# ttl.net
KiCad netlist of a schematic drawn in EAGLE
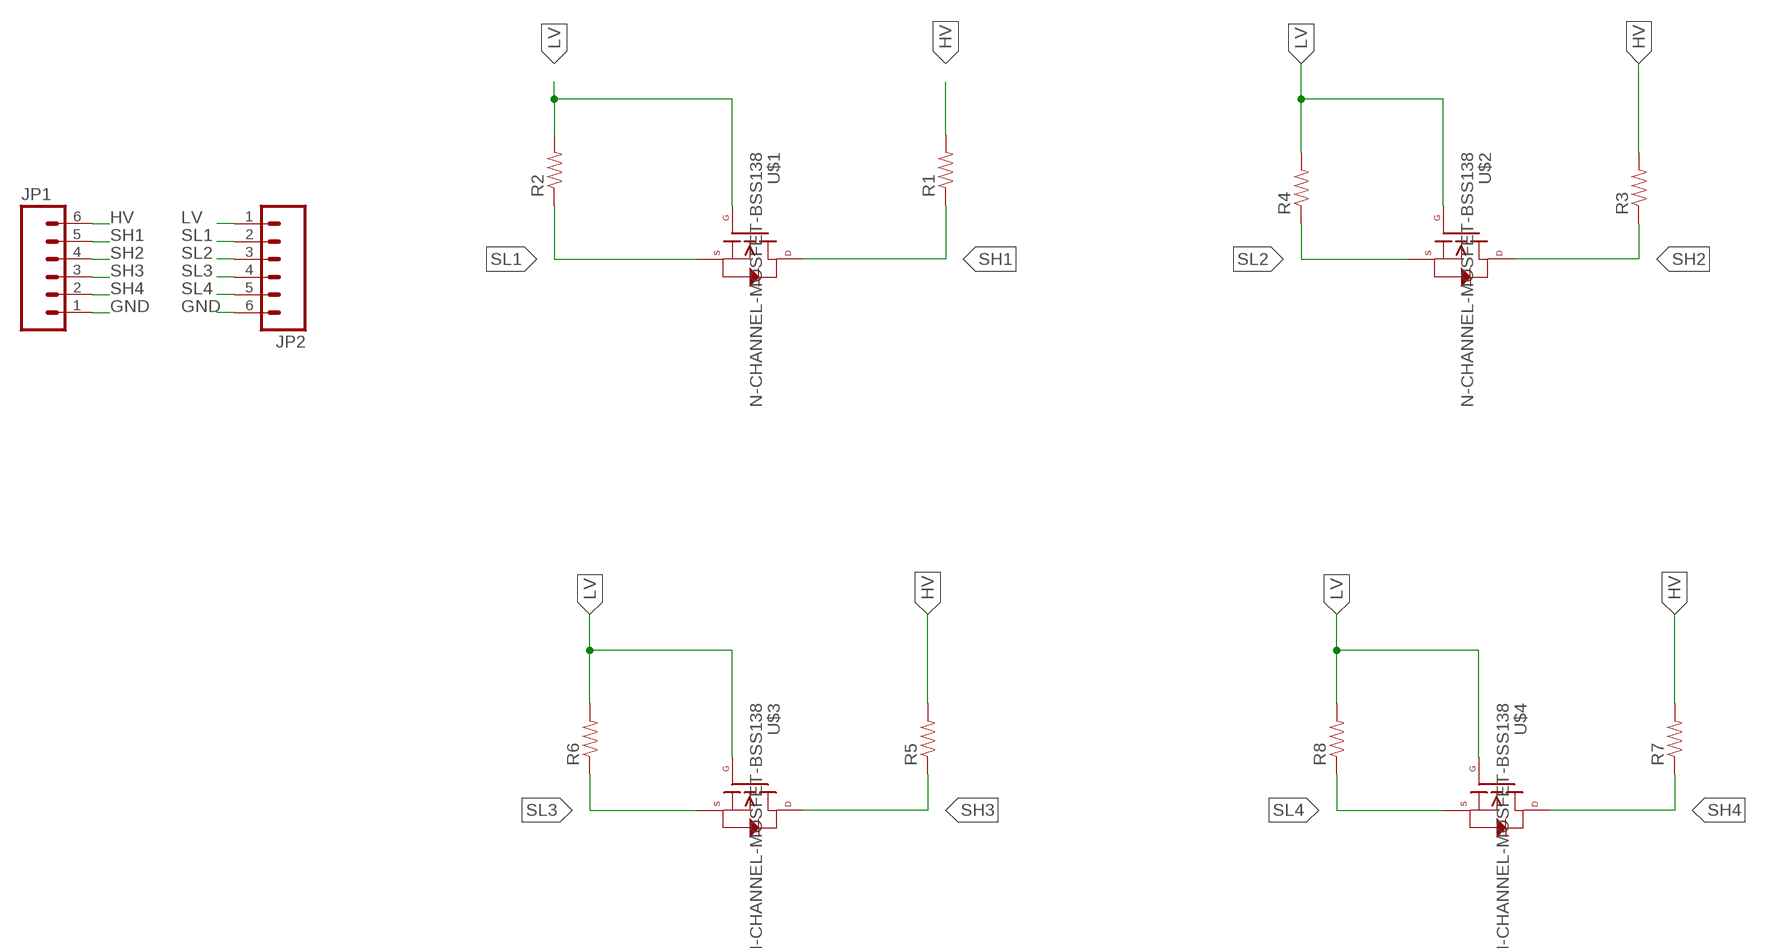
[diagram p0: schematic, sheet 1]

(export (version "E")
  (design (tool "Eeschema 10.0.6"))
  (components
    (comp (ref "JP1")
      (value "M06LOCK_LONGPADS")
      (footprint "eagle-import:1X06_LOCK_LONGPADS")
      (libsource (lib "eagle-import") (part "M06LOCK_LONGPADS"))
    )
    (comp (ref "JP2")
      (value "M06LOCK_LONGPADS")
      (footprint "eagle-import:1X06_LOCK_LONGPADS")
      (libsource (lib "eagle-import") (part "M06LOCK_LONGPADS"))
    )
    (comp (ref "R1")
      (value "RESISTOR0603-RES")
      (footprint "eagle-import:0603-RES")
      (libsource (lib "eagle-import") (part "RESISTOR0603-RES"))
    )
    (comp (ref "R2")
      (value "RESISTOR0603-RES")
      (footprint "eagle-import:0603-RES")
      (libsource (lib "eagle-import") (part "RESISTOR0603-RES"))
    )
    (comp (ref "R3")
      (value "RESISTOR0603-RES")
      (footprint "eagle-import:0603-RES")
      (libsource (lib "eagle-import") (part "RESISTOR0603-RES"))
    )
    (comp (ref "R4")
      (value "RESISTOR0603-RES")
      (footprint "eagle-import:0603-RES")
      (libsource (lib "eagle-import") (part "RESISTOR0603-RES"))
    )
    (comp (ref "R5")
      (value "RESISTOR0603-RES")
      (footprint "eagle-import:0603-RES")
      (libsource (lib "eagle-import") (part "RESISTOR0603-RES"))
    )
    (comp (ref "R6")
      (value "RESISTOR0603-RES")
      (footprint "eagle-import:0603-RES")
      (libsource (lib "eagle-import") (part "RESISTOR0603-RES"))
    )
    (comp (ref "R7")
      (value "RESISTOR0603-RES")
      (footprint "eagle-import:0603-RES")
      (libsource (lib "eagle-import") (part "RESISTOR0603-RES"))
    )
    (comp (ref "R8")
      (value "RESISTOR0603-RES")
      (footprint "eagle-import:0603-RES")
      (libsource (lib "eagle-import") (part "RESISTOR0603-RES"))
    )
    (comp (ref "U$1")
      (value "N-CHANNEL-MOSFET-BSS138")
      (footprint "eagle-import:SOT23-3")
      (libsource (lib "eagle-import") (part "N-CHANNEL-MOSFET-BSS138"))
    )
    (comp (ref "U$2")
      (value "N-CHANNEL-MOSFET-BSS138")
      (footprint "eagle-import:SOT23-3")
      (libsource (lib "eagle-import") (part "N-CHANNEL-MOSFET-BSS138"))
    )
    (comp (ref "U$3")
      (value "N-CHANNEL-MOSFET-BSS138")
      (footprint "eagle-import:SOT23-3")
      (libsource (lib "eagle-import") (part "N-CHANNEL-MOSFET-BSS138"))
    )
    (comp (ref "U$4")
      (value "N-CHANNEL-MOSFET-BSS138")
      (footprint "eagle-import:SOT23-3")
      (libsource (lib "eagle-import") (part "N-CHANNEL-MOSFET-BSS138"))
    )
  )
  (nets
    (net (code "1") (name "/GND") (class "Default")
      (node (ref "JP1") (pin "1") (pinfunction "1_1") (pintype "passive"))
      (node (ref "JP2") (pin "6") (pinfunction "6_6") (pintype "passive"))
    )
    (net (code "2") (name "HV") (class "Default")
      (node (ref "JP1") (pin "6") (pinfunction "6_6") (pintype "passive"))
      (node (ref "R1") (pin "2") (pinfunction "2_2") (pintype "passive"))
      (node (ref "R3") (pin "2") (pinfunction "2_2") (pintype "passive"))
      (node (ref "R5") (pin "2") (pinfunction "2_2") (pintype "passive"))
      (node (ref "R7") (pin "2") (pinfunction "2_2") (pintype "passive"))
    )
    (net (code "3") (name "LV") (class "Default")
      (node (ref "JP2") (pin "1") (pinfunction "1_1") (pintype "passive"))
      (node (ref "R2") (pin "2") (pinfunction "2_2") (pintype "passive"))
      (node (ref "R4") (pin "2") (pinfunction "2_2") (pintype "passive"))
      (node (ref "R6") (pin "2") (pinfunction "2_2") (pintype "passive"))
      (node (ref "R8") (pin "2") (pinfunction "2_2") (pintype "passive"))
      (node (ref "U$1") (pin "1") (pinfunction "G_1") (pintype "passive"))
      (node (ref "U$2") (pin "1") (pinfunction "G_1") (pintype "passive"))
      (node (ref "U$3") (pin "1") (pinfunction "G_1") (pintype "passive"))
      (node (ref "U$4") (pin "1") (pinfunction "G_1") (pintype "passive"))
    )
    (net (code "4") (name "SH1") (class "Default")
      (node (ref "JP1") (pin "5") (pinfunction "5_5") (pintype "passive"))
      (node (ref "R1") (pin "1") (pinfunction "1_1") (pintype "passive"))
      (node (ref "U$1") (pin "3") (pinfunction "D_3") (pintype "passive"))
    )
    (net (code "5") (name "SH2") (class "Default")
      (node (ref "JP1") (pin "4") (pinfunction "4_4") (pintype "passive"))
      (node (ref "R3") (pin "1") (pinfunction "1_1") (pintype "passive"))
      (node (ref "U$2") (pin "3") (pinfunction "D_3") (pintype "passive"))
    )
    (net (code "6") (name "SH3") (class "Default")
      (node (ref "JP1") (pin "3") (pinfunction "3_3") (pintype "passive"))
      (node (ref "R5") (pin "1") (pinfunction "1_1") (pintype "passive"))
      (node (ref "U$3") (pin "3") (pinfunction "D_3") (pintype "passive"))
    )
    (net (code "7") (name "SH4") (class "Default")
      (node (ref "JP1") (pin "2") (pinfunction "2_2") (pintype "passive"))
      (node (ref "R7") (pin "1") (pinfunction "1_1") (pintype "passive"))
      (node (ref "U$4") (pin "3") (pinfunction "D_3") (pintype "passive"))
    )
    (net (code "8") (name "SL1") (class "Default")
      (node (ref "JP2") (pin "2") (pinfunction "2_2") (pintype "passive"))
      (node (ref "R2") (pin "1") (pinfunction "1_1") (pintype "passive"))
      (node (ref "U$1") (pin "2") (pinfunction "S_2") (pintype "passive"))
    )
    (net (code "9") (name "SL2") (class "Default")
      (node (ref "JP2") (pin "3") (pinfunction "3_3") (pintype "passive"))
      (node (ref "R4") (pin "1") (pinfunction "1_1") (pintype "passive"))
      (node (ref "U$2") (pin "2") (pinfunction "S_2") (pintype "passive"))
    )
    (net (code "10") (name "SL3") (class "Default")
      (node (ref "JP2") (pin "4") (pinfunction "4_4") (pintype "passive"))
      (node (ref "R6") (pin "1") (pinfunction "1_1") (pintype "passive"))
      (node (ref "U$3") (pin "2") (pinfunction "S_2") (pintype "passive"))
    )
    (net (code "11") (name "SL4") (class "Default")
      (node (ref "JP2") (pin "5") (pinfunction "5_5") (pintype "passive"))
      (node (ref "R8") (pin "1") (pinfunction "1_1") (pintype "passive"))
      (node (ref "U$4") (pin "2") (pinfunction "S_2") (pintype "passive"))
    )
  )
)
